# WIFI_BLE.net
KiCad netlist of a schematic drawn in Altium Designer
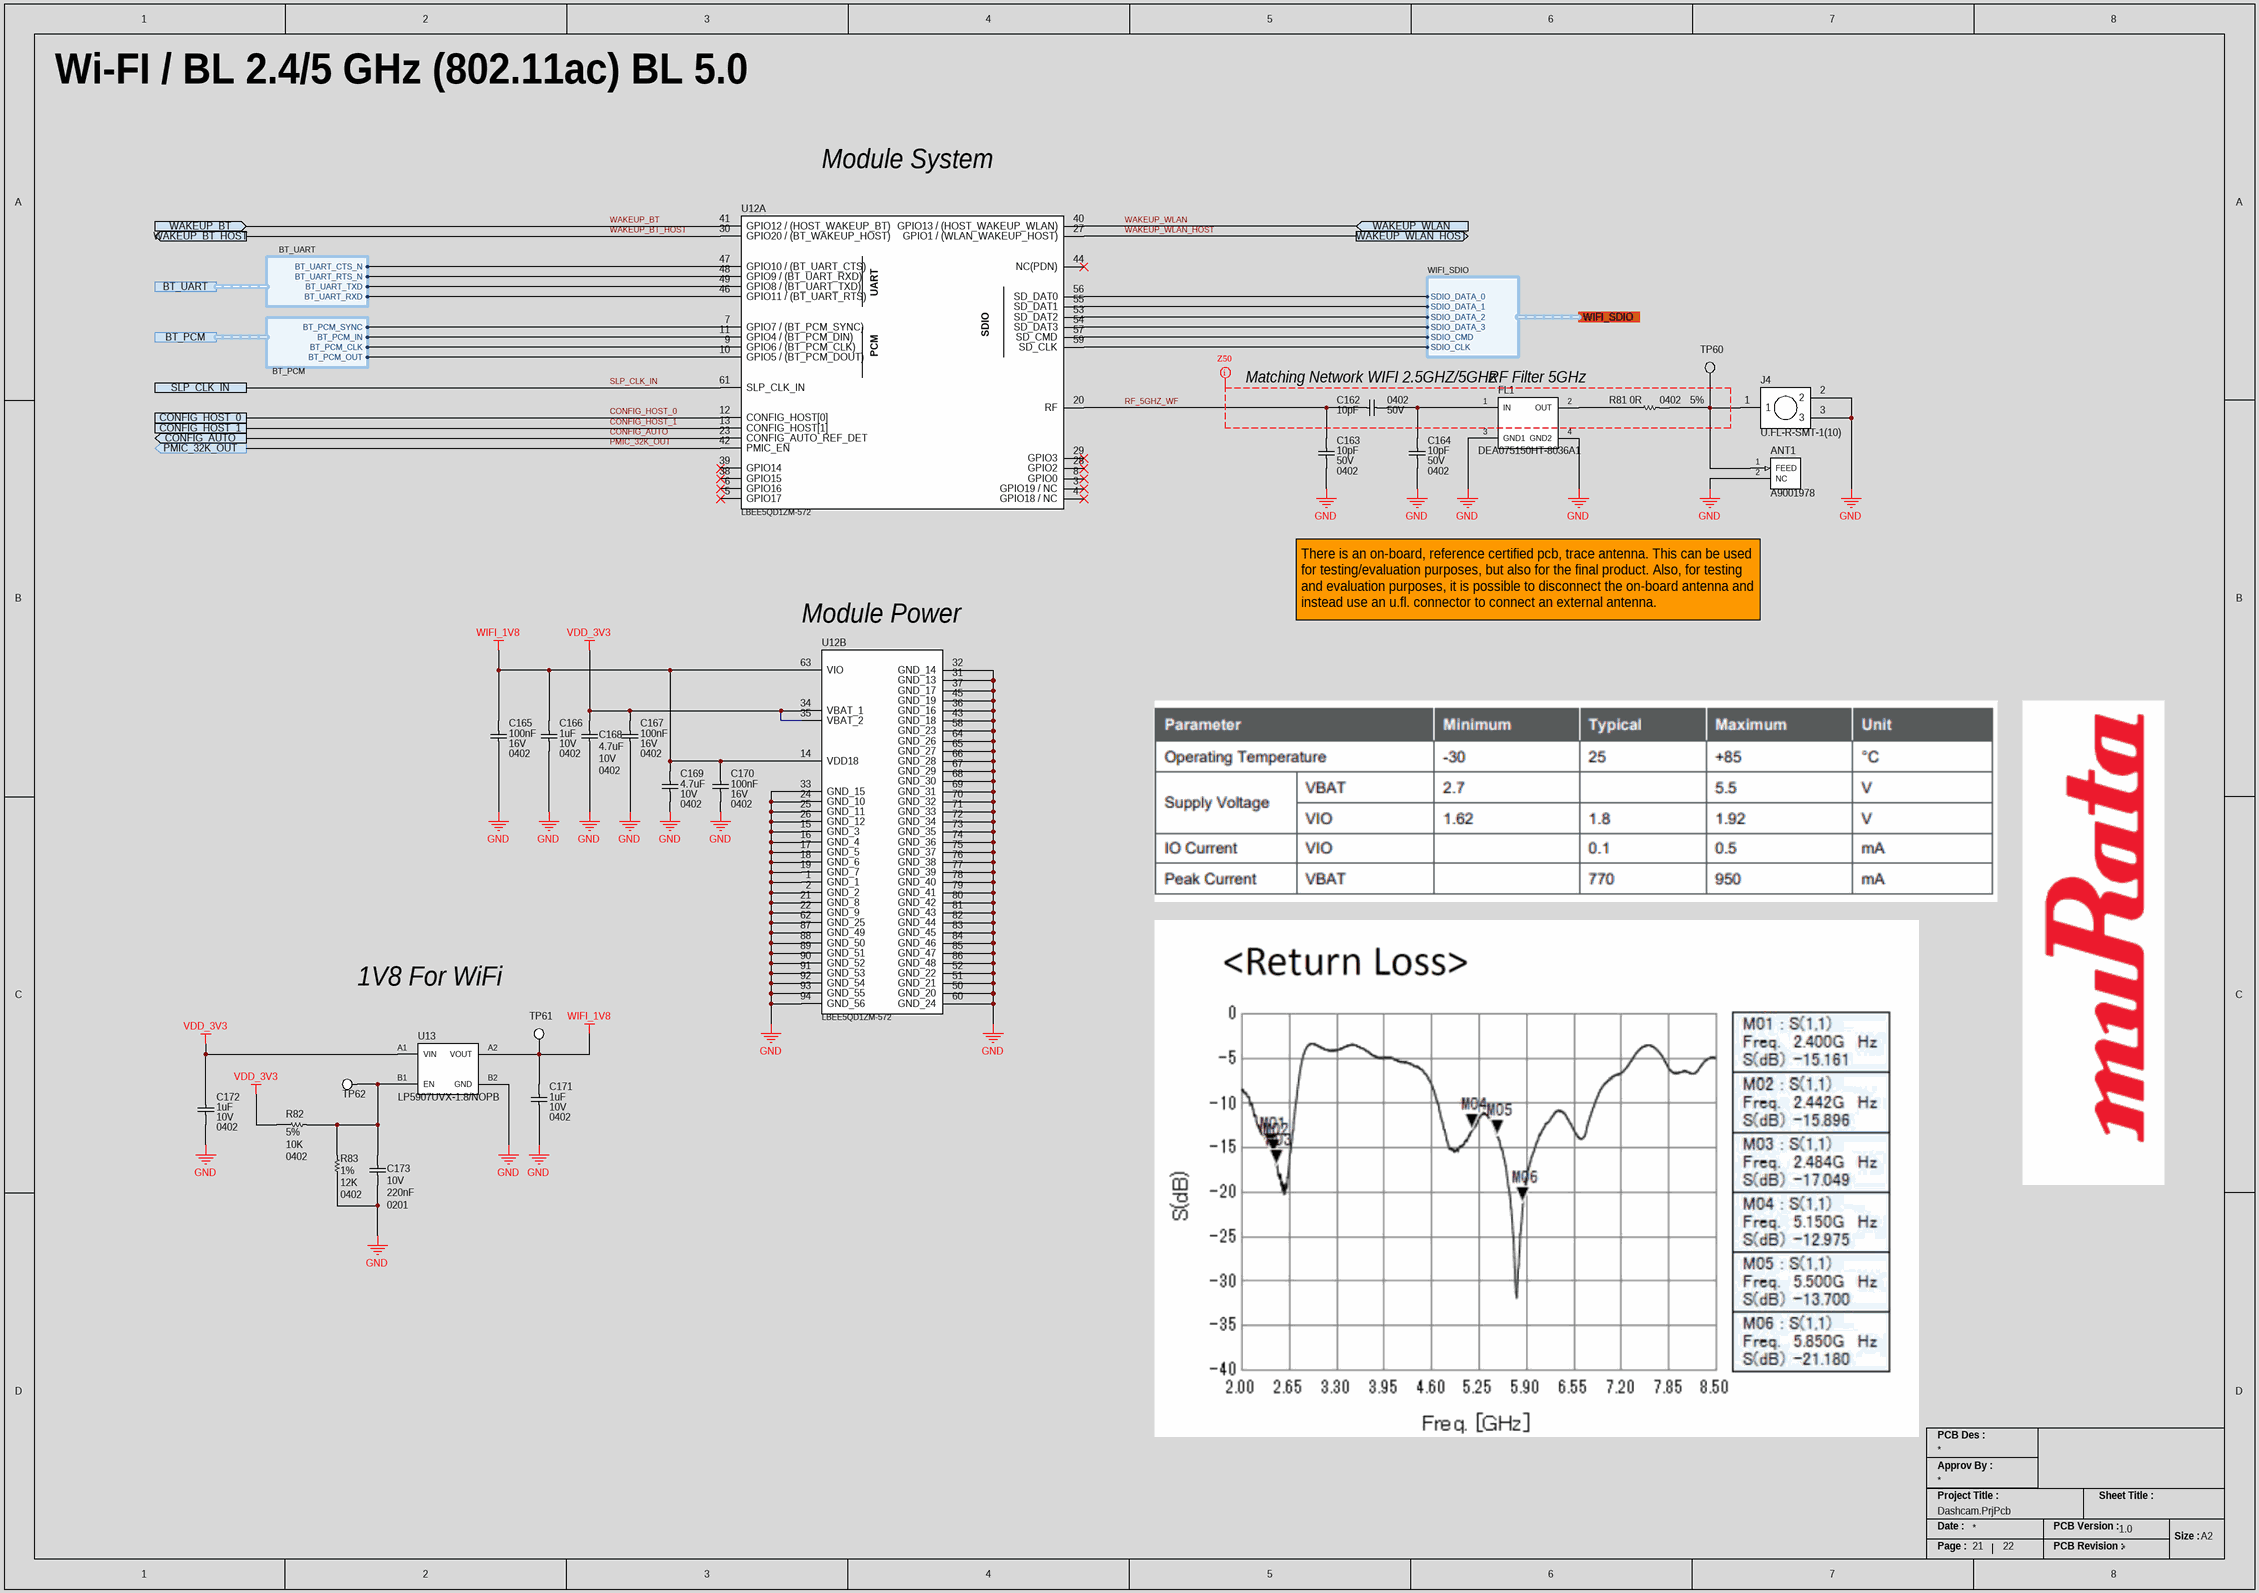
[diagram p0: WIFI_BLE.SchDoc]

(export (version "E")
  (design (tool "Eeschema 10.0.6"))
  (components
    (comp (ref "ANT1")
      (value "A9001978")
      (footprint "ANTENNA_CHIP_ANTC1006X50N")
      (description "Automotive Ultra-small Uwb Or Bl")
      (fields (field (name "MANUFACTURER") "Kyocera AVX"))
      (libsource (lib "Electronic Devices_LIB") (part "ANT_CHIP_2.5GHz_5GHz_A9001978"))
    )
    (comp (ref "C162")
      (value "GJM1555C1H100FB01D")
      (footprint "CAP_0402_CAPC1005X05N")
      (description "Multilayer Ceramic Capacitor, 10 pF, 50 V, ± 1%, C0G (NP0), 0402 [1005 Metric]")
      (fields
        (field (name "MANUFACTURER") "Murata")
        (field (name "TOLERANCE") "1%")
        (field (name "CASE/PACKAGE") "0402")
        (field (name "VOLTAGE RATING") "50V")
        (field (name "CAPACITANCE") "10pF")
      )
      (libsource (lib "Electronic Devices_LIB") (part "CAP_10PF_50V_NP0_0402"))
    )
    (comp (ref "C163")
      (value "GJM1555C1H100FB01D")
      (footprint "CAP_0402_CAPC1005X05N")
      (description "Multilayer Ceramic Capacitor, 10 pF, 50 V, ± 1%, C0G (NP0), 0402 [1005 Metric]")
      (fields
        (field (name "MANUFACTURER") "Murata")
        (field (name "TOLERANCE") "1%")
        (field (name "CASE/PACKAGE") "0402")
        (field (name "VOLTAGE RATING") "50V")
        (field (name "CAPACITANCE") "10pF")
      )
      (libsource (lib "Electronic Devices_LIB") (part "CAP_10PF_50V_NP0_0402"))
    )
    (comp (ref "C164")
      (value "GJM1555C1H100FB01D")
      (footprint "CAP_0402_CAPC1005X05N")
      (description "Multilayer Ceramic Capacitor, 10 pF, 50 V, ± 1%, C0G (NP0), 0402 [1005 Metric]")
      (fields
        (field (name "MANUFACTURER") "Murata")
        (field (name "TOLERANCE") "1%")
        (field (name "CASE/PACKAGE") "0402")
        (field (name "VOLTAGE RATING") "50V")
        (field (name "CAPACITANCE") "10pF")
      )
      (libsource (lib "Electronic Devices_LIB") (part "CAP_10PF_50V_NP0_0402"))
    )
    (comp (ref "C165")
      (value "CL05B104KO5NNNC")
      (footprint "CAP_0402_CAPC1005X05N")
      (description "Multilayer Ceramic Capacitor, 0.1 uF, 16 V, ± 10%, X7R, 0402 [1005 Metric]")
      (fields
        (field (name "MANUFACTURER") "Samsung")
        (field (name "TOLERANCE") "10%")
        (field (name "VOLTAGE RATING") "16V")
        (field (name "CAPACITANCE") "100nF")
        (field (name "CASE/PACKAGE") "0402")
      )
      (libsource (lib "Electronic Devices_LIB") (part "CAP_100NF_16V_X7R_0402"))
    )
    (comp (ref "C166")
      (value "GRM155C81A105KA12D")
      (footprint "CAP_0402_CAPC1005X05N")
      (description "0402 10 V 1 uF ±10% Tolerance X6S Multilayer Ceramic Capacitor")
      (fields
        (field (name "MANUFACTURER") "Murata")
        (field (name "TOLERANCE") "10%")
        (field (name "VOLTAGE RATING") "10V")
        (field (name "CAPACITANCE") "1uF")
        (field (name "CASE/PACKAGE") "0402")
      )
      (libsource (lib "Electronic Devices_LIB") (part "CAP_1UF_10V_X6S_0402"))
    )
    (comp (ref "C167")
      (value "CL05B104KO5NNNC")
      (footprint "CAP_0402_CAPC1005X05N")
      (description "Multilayer Ceramic Capacitor, 0.1 uF, 16 V, ± 10%, X7R, 0402 [1005 Metric]")
      (fields
        (field (name "MANUFACTURER") "Samsung")
        (field (name "TOLERANCE") "10%")
        (field (name "VOLTAGE RATING") "16V")
        (field (name "CAPACITANCE") "100nF")
        (field (name "CASE/PACKAGE") "0402")
      )
      (libsource (lib "Electronic Devices_LIB") (part "CAP_100NF_16V_X7R_0402"))
    )
    (comp (ref "C168")
      (value "CL05A475KP5NRNC")
      (footprint "CAP_0402_CAPC1005X05N")
      (description "Multilayer Ceramic Capacitor, 4.7 uF, 10 V, ± 10%, X5R, 0402 [1005 Metric]")
      (fields
        (field (name "MANUFACTURER") "Samsung")
        (field (name "TOLERANCE") "10%")
        (field (name "CAPACITANCE") "4.7uF")
        (field (name "VOLTAGE RATING") "10V")
        (field (name "CASE/PACKAGE") "0402")
      )
      (libsource (lib "Electronic Devices_LIB") (part "CAP_4.7UF_10V_X5R_0402"))
    )
    (comp (ref "C169")
      (value "CL05A475KP5NRNC")
      (footprint "CAP_0402_CAPC1005X05N")
      (description "Multilayer Ceramic Capacitor, 4.7 uF, 10 V, ± 10%, X5R, 0402 [1005 Metric]")
      (fields
        (field (name "MANUFACTURER") "Samsung")
        (field (name "TOLERANCE") "10%")
        (field (name "CAPACITANCE") "4.7uF")
        (field (name "VOLTAGE RATING") "10V")
        (field (name "CASE/PACKAGE") "0402")
      )
      (libsource (lib "Electronic Devices_LIB") (part "CAP_4.7UF_10V_X5R_0402"))
    )
    (comp (ref "C170")
      (value "CL05B104KO5NNNC")
      (footprint "CAP_0402_CAPC1005X05N")
      (description "Multilayer Ceramic Capacitor, 0.1 uF, 16 V, ± 10%, X7R, 0402 [1005 Metric]")
      (fields
        (field (name "MANUFACTURER") "Samsung")
        (field (name "TOLERANCE") "10%")
        (field (name "VOLTAGE RATING") "16V")
        (field (name "CAPACITANCE") "100nF")
        (field (name "CASE/PACKAGE") "0402")
      )
      (libsource (lib "Electronic Devices_LIB") (part "CAP_100NF_16V_X7R_0402"))
    )
    (comp (ref "C171")
      (value "GRM155C81A105KA12D")
      (footprint "CAP_0402_CAPC1005X05N")
      (description "0402 10 V 1 uF ±10% Tolerance X6S Multilayer Ceramic Capacitor")
      (fields
        (field (name "MANUFACTURER") "Murata")
        (field (name "TOLERANCE") "10%")
        (field (name "VOLTAGE RATING") "10V")
        (field (name "CAPACITANCE") "1uF")
        (field (name "CASE/PACKAGE") "0402")
      )
      (libsource (lib "Electronic Devices_LIB") (part "CAP_1UF_10V_X6S_0402"))
    )
    (comp (ref "C172")
      (value "GRM155C81A105KA12D")
      (footprint "CAP_0402_CAPC1005X05N")
      (description "0402 10 V 1 uF ±10% Tolerance X6S Multilayer Ceramic Capacitor")
      (fields
        (field (name "MANUFACTURER") "Murata")
        (field (name "TOLERANCE") "10%")
        (field (name "VOLTAGE RATING") "10V")
        (field (name "CAPACITANCE") "1uF")
        (field (name "CASE/PACKAGE") "0402")
      )
      (libsource (lib "Electronic Devices_LIB") (part "CAP_1UF_10V_X6S_0402"))
    )
    (comp (ref "C173")
      (value "LMK063BJ224MP-F")
      (footprint "CAP_0201_CAPC0603X03N")
      (description "Multilayer Ceramic Capacitors (High dielectric type), 10V, 0.22 uF, ± 20 %, 0201, X5R, RoHS")
      (fields
        (field (name "MANUFACTURER") "Taiyo Yuden")
        (field (name "TOLERANCE") "20%")
        (field (name "VOLTAGE RATING (DC)") "10V")
        (field (name "CAPACITANCE") "220nF")
        (field (name "CASE/PACKAGE") "0201")
      )
      (libsource (lib "Electronic Devices_LIB") (part "CAP_0.22UF_10V_X5R_0201"))
    )
    (comp (ref "FL1")
      (value "DEA075150HT-8036A1")
      (footprint "RF_FILTER_HP_DEA075150HT8036A1")
      (description "RF Filter High Pass 5150MHz 2400MHz to 2500MHz 0.5dB 50Ohm SMD 4Pin 0202 T/R")
      (fields (field (name "MANUFACTURER") "TDK"))
      (libsource (lib "Electronic Devices_LIB") (part "RF_FILTER_HIGH_PASS_DEA075150HT-8036A1"))
    )
    (comp (ref "J4")
      (value "U.FL-R-SMT-1(10)")
      (footprint "CONN_UFL_U.FL-R-SMT-1(10)")
      (description "RF Connector, 1 Contact(s), Male, Board Mount, Surface Mount Terminal, Receptacle")
      (fields (field (name "MANUFACTURER") "Hirose"))
      (libsource (lib "Electronic Devices_LIB") (part "CONN_UFL_RF_5OR_U.FL-R-SMT-1(10)"))
    )
    (comp (ref "R81")
      (value "ERJ-2GE0R00X")
      (footprint "RES_0402_RESC1005X04N")
      (description "SMD Chip Resistor, Jumper, 0 ohm, 100 mW, 0402 [1005 Metric], Thick Film, General Purpose")
      (fields
        (field (name "MANUFACTURER") "Panasonic")
        (field (name "CASE CODE (IMPERIAL)") "0402")
        (field (name "TOLERANCE") "5%")
        (field (name "RESISTANCE") "0R")
      )
      (libsource (lib "MGP Base_V1.0 RevA") (part "RES_0R_5%_100mW_0402"))
    )
    (comp (ref "R82")
      (value "ERJ-2GEJ103X")
      (footprint "RES_0402_RESC1005X04N")
      (description "Res Thick Film 0402 10K Ohm 5% 1/10W ±200ppm/°C Molded SMD Punched Carrier T/R")
      (fields
        (field (name "MANUFACTURER") "Panasonic")
        (field (name "TOLERANCE") "5%")
        (field (name "RESISTANCE") "10K")
        (field (name "CASE/PACKAGE") "0402")
      )
      (libsource (lib "Electronic Devices_LIB") (part "RES_10K_5%_100mW_0402"))
    )
    (comp (ref "R83")
      (value "ERJ-2RKF1202X")
      (footprint "RES_0402_RESC1005X04N")
      (description "Res Thick Film 0402 12K Ohm 1% 0.1W(1/10W) +/-100ppm/C Molded SMD Automotive Punched T/R")
      (fields
        (field (name "MANUFACTURER") "Panasonic")
        (field (name "TOLERANCE") "1%")
        (field (name "RESISTANCE") "12K")
        (field (name "CASE/PACKAGE") "0402")
      )
      (libsource (lib "Electronic Devices_LIB") (part "RES_12K_1%_100mW_0402"))
    )
    (comp (ref "TP60")
      (value "NO COMPONENT")
      (footprint "TP_PAD_0.5MM_SMD_ROUND")
      (description "Test Point, SMD pad, round, 1.5mm, 1.6mm, 3mm diameter")
      (libsource (lib "Electronic Devices_LIB") (part "TP_PAD_SMD_SMALL"))
    )
    (comp (ref "TP61")
      (value "NO COMPONENT")
      (footprint "TP_PAD_0.8MM_SMD_ROUND")
      (description "Test Point, SMD pad, round, 1.5mm, 1.6mm, 3mm diameter")
      (libsource (lib "Electronic Devices_LIB") (part "TP_PAD_SMD_Round"))
    )
    (comp (ref "TP62")
      (value "NO COMPONENT")
      (footprint "TP_PAD_0.8MM_SMD_ROUND")
      (description "Test Point, SMD pad, round, 1.5mm, 1.6mm, 3mm diameter")
      (libsource (lib "Electronic Devices_LIB") (part "TP_PAD_SMD_Round"))
    )
    (comp (ref "U12")
      (value "LBEE5QD1ZM-572")
      (footprint "IC_WIFI_BLE_LBEE5QD1ZM572")
      (description "2.4 to 5.825GHz Bluetooth WiFi 802.11a/b/g/-c, Bluetooth v5.1 Transceiver Module")
      (fields (field (name "MOUSER PART NUMBER") "81-LBEE5QD1ZM-572") (field (name "MANUFACTURER") "Murata"))
      (libsource (lib "Electronic Devices_LIB") (part "IC_WIFI_BLE_LBEE5QD1ZM-572"))
    )
    (comp (ref "U13")
      (value "LP5907UVX-1.8/NOPB")
      (footprint "IC_REG_LDO_BGA4C35P2X2_71X71X40")
      (description "Low Dropout Regulators(LDO) Positive Fixed 200mV @ 250mA 5.5V 1.8V 250mA DSBGA-4 RoHS")
      (fields (field (name "MANUFACTURER") "Texas Instruments"))
      (libsource (lib "Electronic Devices_LIB") (part "IC_REG_LDO_1.8V_250mA_LP5907UVX-1.8/NOPB"))
    )
  )
  (nets
    (net (code "4") (name "/BT_PCM_CLK") (class "Default")
      (node (ref "U12") (pin "9") (pinfunction "GPIO6_/_(BT_PCM_CLK)_9") (pintype "passive"))
    )
    (net (code "5") (name "/BT_PCM_IN") (class "Default")
      (node (ref "U12") (pin "11") (pinfunction "GPIO4_/_(BT_PCM_DIN)_11") (pintype "passive"))
    )
    (net (code "6") (name "/BT_PCM_OUT") (class "Default")
      (node (ref "U12") (pin "10") (pinfunction "GPIO5_/_(BT_PCM_DOUT)_10") (pintype "passive"))
    )
    (net (code "7") (name "/BT_PCM_SYNC") (class "Default")
      (node (ref "U12") (pin "7") (pinfunction "GPIO7_/_(BT_PCM_SYNC)_7") (pintype "passive"))
    )
    (net (code "8") (name "/BT_UART_CTS_N") (class "Default")
      (node (ref "U12") (pin "47") (pinfunction "GPIO10_/_(BT_UART_CTS)_47") (pintype "passive"))
    )
    (net (code "9") (name "/BT_UART_RTS_N") (class "Default")
      (node (ref "U12") (pin "48") (pinfunction "GPIO9_/_(BT_UART_RXD)_48") (pintype "passive"))
    )
    (net (code "10") (name "/BT_UART_RXD") (class "Default")
      (node (ref "U12") (pin "46") (pinfunction "GPIO11_/_(BT_UART_RTS)_46") (pintype "passive"))
    )
    (net (code "11") (name "/BT_UART_TXD") (class "Default")
      (node (ref "U12") (pin "49") (pinfunction "GPIO8_/_(BT_UART_TXD)_49") (pintype "passive"))
    )
    (net (code "12") (name "/CONFIG_AUTO") (class "Default")
      (node (ref "U12") (pin "23") (pinfunction "CONFIG_AUTO_REF_DET_23") (pintype "passive"))
    )
    (net (code "13") (name "/CONFIG_HOST_0") (class "Default")
      (node (ref "U12") (pin "12") (pinfunction "CONFIG_HOST[0]_12") (pintype "passive"))
    )
    (net (code "14") (name "/CONFIG_HOST_1") (class "Default")
      (node (ref "U12") (pin "13") (pinfunction "CONFIG_HOST[1]_13") (pintype "passive"))
    )
    (net (code "15") (name "/PMIC_32K_OUT") (class "Default")
      (node (ref "U12") (pin "42") (pinfunction "PMIC_EN_42") (pintype "passive"))
    )
    (net (code "16") (name "/RF_5GHZ_WF") (class "Default")
      (node (ref "C162") (pin "1") (pinfunction "1_1") (pintype "passive"))
      (node (ref "C163") (pin "2") (pinfunction "2_2") (pintype "passive"))
      (node (ref "U12") (pin "20") (pinfunction "RF_20") (pintype "passive"))
    )
    (net (code "17") (name "/SDIO_CLK") (class "Default")
      (node (ref "U12") (pin "59") (pinfunction "SD_CLK_59") (pintype "passive"))
    )
    (net (code "18") (name "/SDIO_CMD") (class "Default")
      (node (ref "U12") (pin "57") (pinfunction "SD_CMD_57") (pintype "passive"))
    )
    (net (code "19") (name "/SDIO_DATA_0") (class "Default")
      (node (ref "U12") (pin "56") (pinfunction "SD_DAT0_56") (pintype "passive"))
    )
    (net (code "20") (name "/SDIO_DATA_1") (class "Default")
      (node (ref "U12") (pin "55") (pinfunction "SD_DAT1_55") (pintype "passive"))
    )
    (net (code "21") (name "/SDIO_DATA_2") (class "Default")
      (node (ref "U12") (pin "53") (pinfunction "SD_DAT2_53") (pintype "passive"))
    )
    (net (code "22") (name "/SDIO_DATA_3") (class "Default")
      (node (ref "U12") (pin "54") (pinfunction "SD_DAT3_54") (pintype "passive"))
    )
    (net (code "23") (name "/SLP_CLK_IN") (class "Default")
      (node (ref "U12") (pin "61") (pinfunction "SLP_CLK_IN_61") (pintype "passive"))
    )
    (net (code "24") (name "/WAKEUP_BT") (class "Default")
      (node (ref "U12") (pin "41") (pinfunction "GPIO12_/_(HOST_WAKEUP_BT)_41") (pintype "passive"))
    )
    (net (code "25") (name "/WAKEUP_BT_HOST") (class "Default")
      (node (ref "U12") (pin "30") (pinfunction "GPIO20_/_(BT_WAKEUP_HOST)_30") (pintype "passive"))
    )
    (net (code "26") (name "/WAKEUP_WLAN") (class "Default")
      (node (ref "U12") (pin "40") (pinfunction "GPIO13_/_(HOST_WAKEUP_WLAN)_40") (pintype "passive"))
    )
    (net (code "27") (name "/WAKEUP_WLAN_HOST") (class "Default")
      (node (ref "U12") (pin "27") (pinfunction "GPIO1_/_(WLAN_WAKEUP_HOST)_27") (pintype "passive"))
    )
    (net (code "31") (name "GND") (class "Default")
      (node (ref "ANT1") (pin "2") (pinfunction "NC_2") (pintype "passive"))
      (node (ref "C163") (pin "1") (pinfunction "1_1") (pintype "passive"))
      (node (ref "C164") (pin "1") (pinfunction "1_1") (pintype "passive"))
      (node (ref "C165") (pin "1") (pinfunction "1_1") (pintype "passive"))
      (node (ref "C166") (pin "1") (pinfunction "1_1") (pintype "passive"))
      (node (ref "C167") (pin "1") (pinfunction "1_1") (pintype "passive"))
      (node (ref "C168") (pin "1") (pinfunction "1_1") (pintype "passive"))
      (node (ref "C169") (pin "1") (pinfunction "1_1") (pintype "passive"))
      (node (ref "C170") (pin "1") (pinfunction "1_1") (pintype "passive"))
      (node (ref "C171") (pin "1") (pinfunction "1_1") (pintype "passive"))
      (node (ref "C172") (pin "1") (pinfunction "1_1") (pintype "passive"))
      (node (ref "C173") (pin "1") (pinfunction "1_1") (pintype "passive"))
      (node (ref "FL1") (pin "3") (pinfunction "GND1_3") (pintype "passive"))
      (node (ref "FL1") (pin "4") (pinfunction "GND2_4") (pintype "passive"))
      (node (ref "J4") (pin "2") (pinfunction "2_2") (pintype "passive"))
      (node (ref "J4") (pin "3") (pinfunction "3_3") (pintype "passive"))
      (node (ref "R83") (pin "1") (pinfunction "1_1") (pintype "passive"))
      (node (ref "U12") (pin "1") (pinfunction "GND_1_1") (pintype "passive"))
      (node (ref "U12") (pin "15") (pinfunction "GND_3_15") (pintype "passive"))
      (node (ref "U12") (pin "16") (pinfunction "GND_4_16") (pintype "passive"))
      (node (ref "U12") (pin "17") (pinfunction "GND_5_17") (pintype "passive"))
      (node (ref "U12") (pin "18") (pinfunction "GND_6_18") (pintype "passive"))
      (node (ref "U12") (pin "19") (pinfunction "GND_7_19") (pintype "passive"))
      (node (ref "U12") (pin "2") (pinfunction "GND_2_2") (pintype "passive"))
      (node (ref "U12") (pin "21") (pinfunction "GND_8_21") (pintype "passive"))
      (node (ref "U12") (pin "22") (pinfunction "GND_9_22") (pintype "passive"))
      (node (ref "U12") (pin "24") (pinfunction "GND_10_24") (pintype "passive"))
      (node (ref "U12") (pin "25") (pinfunction "GND_11_25") (pintype "passive"))
      (node (ref "U12") (pin "26") (pinfunction "GND_12_26") (pintype "passive"))
      (node (ref "U12") (pin "31") (pinfunction "GND_13_31") (pintype "passive"))
      (node (ref "U12") (pin "32") (pinfunction "GND_14_32") (pintype "passive"))
      (node (ref "U12") (pin "33") (pinfunction "GND_15_33") (pintype "passive"))
      (node (ref "U12") (pin "36") (pinfunction "GND_16_36") (pintype "passive"))
      (node (ref "U12") (pin "37") (pinfunction "GND_17_37") (pintype "passive"))
      (node (ref "U12") (pin "43") (pinfunction "GND_18_43") (pintype "passive"))
      (node (ref "U12") (pin "45") (pinfunction "GND_19_45") (pintype "passive"))
      (node (ref "U12") (pin "50") (pinfunction "GND_20_50") (pintype "passive"))
      (node (ref "U12") (pin "51") (pinfunction "GND_21_51") (pintype "passive"))
      (node (ref "U12") (pin "52") (pinfunction "GND_22_52") (pintype "passive"))
      (node (ref "U12") (pin "58") (pinfunction "GND_23_58") (pintype "passive"))
      (node (ref "U12") (pin "60") (pinfunction "GND_24_60") (pintype "passive"))
      (node (ref "U12") (pin "62") (pinfunction "GND_25_62") (pintype "passive"))
      (node (ref "U12") (pin "64") (pinfunction "GND_26_64") (pintype "passive"))
      (node (ref "U12") (pin "65") (pinfunction "GND_27_65") (pintype "passive"))
      (node (ref "U12") (pin "66") (pinfunction "GND_28_66") (pintype "passive"))
      (node (ref "U12") (pin "67") (pinfunction "GND_29_67") (pintype "passive"))
      (node (ref "U12") (pin "68") (pinfunction "GND_30_68") (pintype "passive"))
      (node (ref "U12") (pin "69") (pinfunction "GND_31_69") (pintype "passive"))
      (node (ref "U12") (pin "70") (pinfunction "GND_32_70") (pintype "passive"))
      (node (ref "U12") (pin "71") (pinfunction "GND_33_71") (pintype "passive"))
      (node (ref "U12") (pin "72") (pinfunction "GND_34_72") (pintype "passive"))
      (node (ref "U12") (pin "73") (pinfunction "GND_35_73") (pintype "passive"))
      (node (ref "U12") (pin "74") (pinfunction "GND_36_74") (pintype "passive"))
      (node (ref "U12") (pin "75") (pinfunction "GND_37_75") (pintype "passive"))
      (node (ref "U12") (pin "76") (pinfunction "GND_38_76") (pintype "passive"))
      (node (ref "U12") (pin "77") (pinfunction "GND_39_77") (pintype "passive"))
      (node (ref "U12") (pin "78") (pinfunction "GND_40_78") (pintype "passive"))
      (node (ref "U12") (pin "79") (pinfunction "GND_41_79") (pintype "passive"))
      (node (ref "U12") (pin "80") (pinfunction "GND_42_80") (pintype "passive"))
      (node (ref "U12") (pin "81") (pinfunction "GND_43_81") (pintype "passive"))
      (node (ref "U12") (pin "82") (pinfunction "GND_44_82") (pintype "passive"))
      (node (ref "U12") (pin "83") (pinfunction "GND_45_83") (pintype "passive"))
      (node (ref "U12") (pin "84") (pinfunction "GND_46_84") (pintype "passive"))
      (node (ref "U12") (pin "85") (pinfunction "GND_47_85") (pintype "passive"))
      (node (ref "U12") (pin "86") (pinfunction "GND_48_86") (pintype "passive"))
      (node (ref "U12") (pin "87") (pinfunction "GND_49_87") (pintype "passive"))
      (node (ref "U12") (pin "88") (pinfunction "GND_50_88") (pintype "passive"))
      (node (ref "U12") (pin "89") (pinfunction "GND_51_89") (pintype "passive"))
      (node (ref "U12") (pin "90") (pinfunction "GND_52_90") (pintype "passive"))
      (node (ref "U12") (pin "91") (pinfunction "GND_53_91") (pintype "passive"))
      (node (ref "U12") (pin "92") (pinfunction "GND_54_92") (pintype "passive"))
      (node (ref "U12") (pin "93") (pinfunction "GND_55_93") (pintype "passive"))
      (node (ref "U12") (pin "94") (pinfunction "GND_56_94") (pintype "passive"))
      (node (ref "U13") (pin "B2") (pinfunction "GND_B2") (pintype "passive"))
    )
    (net (code "32") (name "Net-(ANT1-FEED)") (class "Default")
      (node (ref "ANT1") (pin "1") (pinfunction "FEED_1") (pintype "input"))
      (node (ref "J4") (pin "1") (pinfunction "1_1") (pintype "passive"))
      (node (ref "R81") (pin "2") (pinfunction "2_2") (pintype "passive"))
      (node (ref "TP60") (pin "1") (pinfunction "1_1") (pintype "passive"))
    )
    (net (code "33") (name "Net-(FL1-IN)") (class "Default")
      (node (ref "C162") (pin "2") (pinfunction "2_2") (pintype "passive"))
      (node (ref "C164") (pin "2") (pinfunction "2_2") (pintype "passive"))
      (node (ref "FL1") (pin "1") (pinfunction "IN_1") (pintype "passive"))
    )
    (net (code "34") (name "Net-(FL1-OUT)") (class "Default")
      (node (ref "FL1") (pin "2") (pinfunction "OUT_2") (pintype "passive"))
      (node (ref "R81") (pin "1") (pinfunction "1_1") (pintype "passive"))
    )
    (net (code "35") (name "Net-(U13-EN)") (class "Default")
      (node (ref "C173") (pin "2") (pinfunction "2_2") (pintype "passive"))
      (node (ref "R82") (pin "2") (pinfunction "2_2") (pintype "passive"))
      (node (ref "R83") (pin "2") (pinfunction "2_2") (pintype "passive"))
      (node (ref "TP62") (pin "1") (pinfunction "1_1") (pintype "passive"))
      (node (ref "U13") (pin "B1") (pinfunction "EN_B1") (pintype "passive"))
    )
    (net (code "36") (name "VDD_3V3") (class "Default")
      (node (ref "C167") (pin "2") (pinfunction "2_2") (pintype "passive"))
      (node (ref "C168") (pin "2") (pinfunction "2_2") (pintype "passive"))
      (node (ref "C172") (pin "2") (pinfunction "2_2") (pintype "passive"))
      (node (ref "R82") (pin "1") (pinfunction "1_1") (pintype "passive"))
      (node (ref "U12") (pin "34") (pinfunction "VBAT_1_34") (pintype "passive"))
      (node (ref "U12") (pin "35") (pinfunction "VBAT_2_35") (pintype "passive"))
      (node (ref "U13") (pin "A1") (pinfunction "VIN_A1") (pintype "passive"))
    )
    (net (code "37") (name "WIFI_1V8") (class "Default")
      (node (ref "C165") (pin "2") (pinfunction "2_2") (pintype "passive"))
      (node (ref "C166") (pin "2") (pinfunction "2_2") (pintype "passive"))
      (node (ref "C169") (pin "2") (pinfunction "2_2") (pintype "passive"))
      (node (ref "C170") (pin "2") (pinfunction "2_2") (pintype "passive"))
      (node (ref "C171") (pin "2") (pinfunction "2_2") (pintype "passive"))
      (node (ref "TP61") (pin "1") (pinfunction "1_1") (pintype "passive"))
      (node (ref "U12") (pin "14") (pinfunction "VDD18_14") (pintype "passive"))
      (node (ref "U12") (pin "63") (pinfunction "VIO_63") (pintype "passive"))
      (node (ref "U13") (pin "A2") (pinfunction "VOUT_A2") (pintype "passive"))
    )
    (net (code "38") (name "unconnected-(U12A-GPIO0-Pad8)") (class "Default")
      (node (ref "U12") (pin "8") (pinfunction "GPIO0_8") (pintype "passive+no_connect"))
    )
    (net (code "39") (name "unconnected-(U12A-GPIO2-Pad28)") (class "Default")
      (node (ref "U12") (pin "28") (pinfunction "GPIO2_28") (pintype "passive+no_connect"))
    )
    (net (code "40") (name "unconnected-(U12A-GPIO3-Pad29)") (class "Default")
      (node (ref "U12") (pin "29") (pinfunction "GPIO3_29") (pintype "passive+no_connect"))
    )
    (net (code "41") (name "unconnected-(U12A-GPIO14-Pad39)") (class "Default")
      (node (ref "U12") (pin "39") (pinfunction "GPIO14_39") (pintype "passive+no_connect"))
    )
    (net (code "42") (name "unconnected-(U12A-GPIO15-Pad38)") (class "Default")
      (node (ref "U12") (pin "38") (pinfunction "GPIO15_38") (pintype "passive+no_connect"))
    )
    (net (code "43") (name "unconnected-(U12A-GPIO16-Pad6)") (class "Default")
      (node (ref "U12") (pin "6") (pinfunction "GPIO16_6") (pintype "passive+no_connect"))
    )
    (net (code "44") (name "unconnected-(U12A-GPIO17-Pad5)") (class "Default")
      (node (ref "U12") (pin "5") (pinfunction "GPIO17_5") (pintype "passive+no_connect"))
    )
    (net (code "45") (name "unconnected-(U12A-GPIO18_{slash}_NC-Pad4)") (class "Default")
      (node (ref "U12") (pin "4") (pinfunction "GPIO18_/_NC_4") (pintype "passive+no_connect"))
    )
    (net (code "46") (name "unconnected-(U12A-GPIO19_{slash}_NC-Pad3)") (class "Default")
      (node (ref "U12") (pin "3") (pinfunction "GPIO19_/_NC_3") (pintype "passive+no_connect"))
    )
    (net (code "47") (name "unconnected-(U12A-NC(PDN)-Pad44)") (class "Default")
      (node (ref "U12") (pin "44") (pinfunction "NC(PDN)_44") (pintype "passive+no_connect"))
    )
  )
)
